# smd_res_breakout.net
KiCad netlist of a schematic drawn in EAGLE
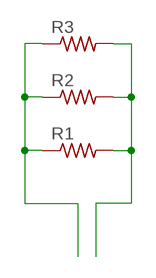
[diagram p0: schematic, sheet 1]

(export (version "E")
  (design (tool "Eeschema 10.0.6"))
  (components
    (comp (ref "R1")
      (value "R-US_R1206")
      (footprint "eagle-import:R1206")
      (libsource (lib "eagle-import") (part "R-US_R1206"))
    )
    (comp (ref "R2")
      (value "R-US_R0805")
      (footprint "eagle-import:R0805")
      (libsource (lib "eagle-import") (part "R-US_R0805"))
    )
    (comp (ref "R3")
      (value "R-US_R0603")
      (footprint "eagle-import:R0603")
      (libsource (lib "eagle-import") (part "R-US_R0603"))
    )
  )
  (nets
    (net (code "1") (name "Net-(R1-Pad1)") (class "Default")
      (node (ref "R1") (pin "1") (pinfunction "1_1") (pintype "passive"))
      (node (ref "R2") (pin "1") (pinfunction "1_1") (pintype "passive"))
      (node (ref "R3") (pin "1") (pinfunction "1_1") (pintype "passive"))
    )
    (net (code "2") (name "Net-(R1-Pad2)") (class "Default")
      (node (ref "R1") (pin "2") (pinfunction "2_2") (pintype "passive"))
      (node (ref "R2") (pin "2") (pinfunction "2_2") (pintype "passive"))
      (node (ref "R3") (pin "2") (pinfunction "2_2") (pintype "passive"))
    )
  )
)
